# ProPrj_GTStoppuhr_v0_1.net
KiCad netlist of a schematic drawn in EasyEDA Pro
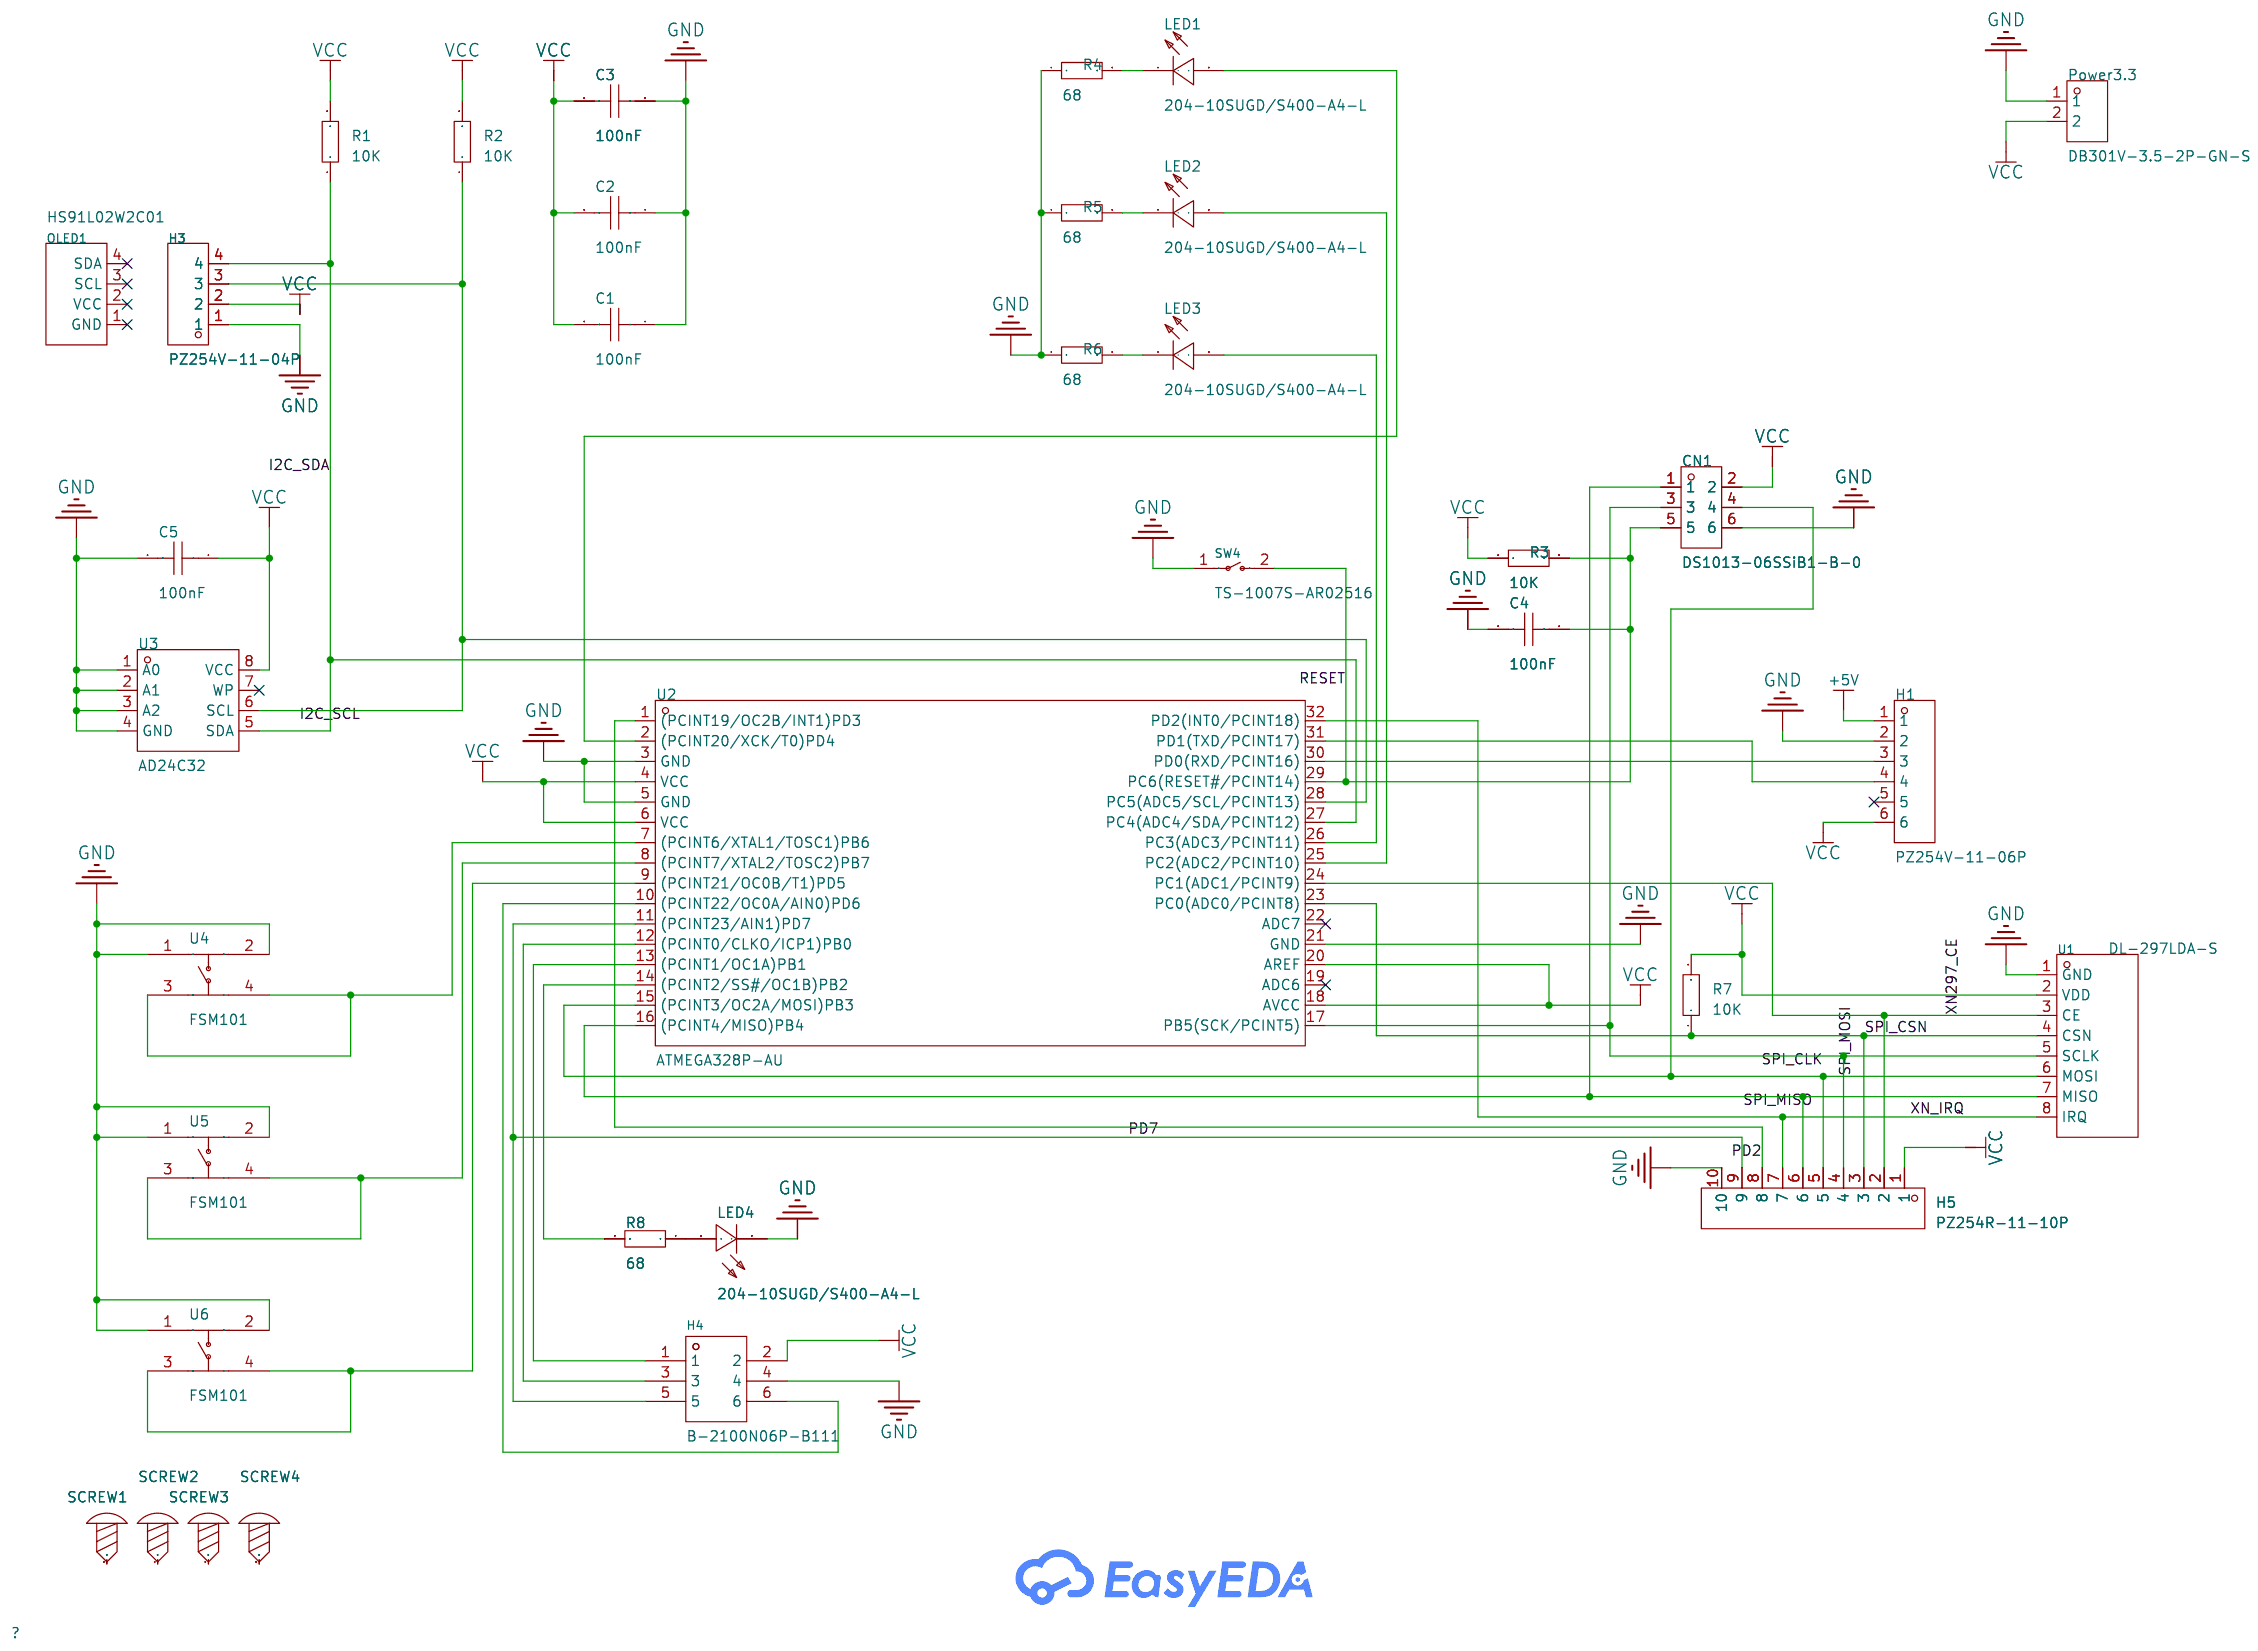
[diagram p0: schematic sheet]

(export (version "E")
  (design (tool "Eeschema 10.0.6"))
  (components
    (comp (ref "C1")
      (value "100nF")
      (footprint "easyedapro:C0603")
      (libsource (lib "easyedapro") (part "CAP"))
    )
    (comp (ref "C2")
      (value "100nF")
      (footprint "easyedapro:C0603")
      (libsource (lib "easyedapro") (part "CAP"))
    )
    (comp (ref "C3")
      (value "100nF")
      (footprint "easyedapro:C0603")
      (libsource (lib "easyedapro") (part "CAP"))
    )
    (comp (ref "C4")
      (value "100nF")
      (footprint "easyedapro:C0603")
      (libsource (lib "easyedapro") (part "CAP"))
    )
    (comp (ref "C5")
      (value "100nF")
      (footprint "easyedapro:C0603")
      (libsource (lib "easyedapro") (part "CAP"))
    )
    (comp (ref "CN1")
      (value "DS1013-06SSiB1-B-0")
      (footprint "easyedapro:IDC-TH_6P-P2.54_DS1013-06SSIB1-B-0")
      (fields (field (name "Manufacturer") "CONNFLY"))
      (libsource (lib "easyedapro") (part "DS1013-06SSIB1-B-0"))
    )
    (comp (ref "H1")
      (value "PZ254V-11-06P")
      (footprint "easyedapro:HDR-TH_6P-P2.54-V-M")
      (fields (field (name "Manufacturer") "XFCN(兴飞)"))
      (libsource (lib "easyedapro") (part "PZ254V-11-06P"))
    )
    (comp (ref "H3")
      (value "PZ254V-11-04P")
      (footprint "easyedapro:HDR-TH_4P-P2.54-V-M")
      (fields (field (name "Manufacturer") "XFCN(兴飞)"))
      (libsource (lib "easyedapro") (part "PZ254V-11-04P_C2691448"))
    )
    (comp (ref "H4")
      (value "B-2100N06P-B111")
      (footprint "easyedapro:HDR-SMD_6P-P2.54-V-M-R2-C3-S2.54-LS7.3")
      (fields (field (name "Manufacturer") "Ckmtw(灿科盟)"))
      (libsource (lib "easyedapro") (part "210SMT-2*3P Gold-plated black"))
    )
    (comp (ref "H5")
      (value "PZ254R-11-10P")
      (footprint "easyedapro:HDR-TH_10P-P2.54-H-M-W10.4")
      (fields (field (name "Manufacturer") "XFCN(兴飞)"))
      (libsource (lib "easyedapro") (part "PZ254R-11-10P"))
    )
    (comp (ref "LED1")
      (value "204-10SUGD/S400-A4-L")
      (footprint "easyedapro:LED-TH_BD3.9-P2.54-RD")
      (fields (field (name "Manufacturer") "EVERLIGHT(亿光)"))
      (libsource (lib "easyedapro") (part "204-10SUGD/S400-A4-L"))
    )
    (comp (ref "LED2")
      (value "204-10SUGD/S400-A4-L")
      (footprint "easyedapro:LED-TH_BD3.9-P2.54-RD")
      (fields (field (name "Manufacturer") "EVERLIGHT(亿光)"))
      (libsource (lib "easyedapro") (part "204-10SUGD/S400-A4-L"))
    )
    (comp (ref "LED3")
      (value "204-10SUGD/S400-A4-L")
      (footprint "easyedapro:LED-TH_BD3.9-P2.54-RD")
      (fields (field (name "Manufacturer") "EVERLIGHT(亿光)"))
      (libsource (lib "easyedapro") (part "204-10SUGD/S400-A4-L"))
    )
    (comp (ref "LED4")
      (value "204-10SUGD/S400-A4-L")
      (footprint "easyedapro:LED-TH_BD3.9-P2.54-RD")
      (fields (field (name "Manufacturer") "EVERLIGHT(亿光)"))
      (libsource (lib "easyedapro") (part "204-10SUGD/S400-A4-L"))
    )
    (comp (ref "OLED1")
      (value "HS91L02W2C01")
      (footprint "easyedapro:OLED-TH_L38.0-W12.0_HS91L02W2C01")
      (fields (field (name "Manufacturer") "HS(汉昇)"))
      (libsource (lib "easyedapro") (part "HS91L02W2C01"))
    )
    (comp (ref "Power3.3")
      (value "DB301V-3.5-2P-GN-S")
      (footprint "easyedapro:CONN-TH_2P-P3.50_DIBO_DB127S-3.5-2P-GN")
      (fields (field (name "Manufacturer") "DORABO(地博电气)"))
      (libsource (lib "easyedapro") (part "DB127S-3.5-2P-GN"))
    )
    (comp (ref "R1") (value "10K") (footprint "easyedapro:R0603") (libsource (lib "easyedapro") (part "Res")))
    (comp (ref "R2") (value "10K") (footprint "easyedapro:R0603") (libsource (lib "easyedapro") (part "Res")))
    (comp (ref "R3") (value "10K") (footprint "easyedapro:R0603") (libsource (lib "easyedapro") (part "Res")))
    (comp (ref "R4") (value "68") (footprint "easyedapro:R0603") (libsource (lib "easyedapro") (part "Res")))
    (comp (ref "R5") (value "68") (footprint "easyedapro:R0603") (libsource (lib "easyedapro") (part "Res")))
    (comp (ref "R6") (value "68") (footprint "easyedapro:R0603") (libsource (lib "easyedapro") (part "Res")))
    (comp (ref "R7") (value "10K") (footprint "easyedapro:R0603") (libsource (lib "easyedapro") (part "Res")))
    (comp (ref "R8") (value "68") (footprint "easyedapro:R0603") (libsource (lib "easyedapro") (part "Res")))
    (comp (ref "SCREW1")
      (value "~")
      (footprint "easyedapro:Screw-Hole-M4")
      (description "Screw-Hole-M4")
      (libsource (lib "easyedapro") (part "Screw-Hole"))
    )
    (comp (ref "SCREW2")
      (value "~")
      (footprint "easyedapro:Screw-Hole-M4")
      (description "Screw-Hole-M4")
      (libsource (lib "easyedapro") (part "Screw-Hole"))
    )
    (comp (ref "SCREW3")
      (value "~")
      (footprint "easyedapro:Screw-Hole-M4")
      (description "Screw-Hole-M4")
      (libsource (lib "easyedapro") (part "Screw-Hole"))
    )
    (comp (ref "SCREW4")
      (value "~")
      (footprint "easyedapro:Screw-Hole-M4")
      (description "Screw-Hole-M4")
      (libsource (lib "easyedapro") (part "Screw-Hole"))
    )
    (comp (ref "SW4")
      (value "TS-1007S-AR02516")
      (footprint "easyedapro:SW-SMD_L6.1-W3.6-LS7.9")
      (fields (field (name "Manufacturer") "XUNPU(讯普)"))
      (libsource (lib "easyedapro") (part "TS-1007S-AR02516"))
    )
    (comp (ref "U1")
      (value "DL-297LDA-S")
      (footprint "easyedapro:WIRELM-SMD_DL-297LDA-S")
      (fields (field (name "Manufacturer") "DreamLNK(骏晔科技)"))
      (libsource (lib "easyedapro") (part "DL-297LDA-S"))
    )
    (comp (ref "U2")
      (value "ATMEGA328P-AU")
      (footprint "easyedapro:TQFP-32_L7.0-W7.0-P0.80-LS9.0-BL")
      (fields (field (name "Manufacturer") "MICROCHIP(美国微芯)"))
      (libsource (lib "easyedapro") (part "ATMEGA328P-AU"))
    )
    (comp (ref "U3")
      (value "AD24C32")
      (footprint "easyedapro:SOIC-8_L4.9-W3.9-P1.27-LS6.2-BL")
      (fields (field (name "Manufacturer") "IDCHIP(英锐芯)"))
      (libsource (lib "easyedapro") (part "AD24C32"))
    )
    (comp (ref "U4")
      (value "FSM101")
      (footprint "easyedapro:SW-TH_4P-L12.0-W12.0-P5.00-LS12.5")
      (fields (field (name "Manufacturer") "TE Connectivity(泰科电子)"))
      (libsource (lib "easyedapro") (part "FSM101"))
    )
    (comp (ref "U5")
      (value "FSM101")
      (footprint "easyedapro:SW-TH_4P-L12.0-W12.0-P5.00-LS12.5")
      (fields (field (name "Manufacturer") "TE Connectivity(泰科电子)"))
      (libsource (lib "easyedapro") (part "FSM101"))
    )
    (comp (ref "U6")
      (value "FSM101")
      (footprint "easyedapro:SW-TH_4P-L12.0-W12.0-P5.00-LS12.5")
      (fields (field (name "Manufacturer") "TE Connectivity(泰科电子)"))
      (libsource (lib "easyedapro") (part "FSM101"))
    )
  )
  (nets
    (net (code "1") (name "+5V") (class "Default")
      (node (ref "H1") (pin "1") (pinfunction "1_1") (pintype "unspecified"))
    )
    (net (code "2") (name "/I2C_SCL") (class "Default")
      (node (ref "H3") (pin "3") (pinfunction "3_3") (pintype "input"))
      (node (ref "R2") (pin "1") (pinfunction "1_1") (pintype "input"))
      (node (ref "U2") (pin "28") (pinfunction "PC5(ADC5/SCL/PCINT13)_28") (pintype "unspecified"))
      (node (ref "U3") (pin "6") (pinfunction "SCL_6") (pintype "unspecified"))
    )
    (net (code "3") (name "/I2C_SDA") (class "Default")
      (node (ref "H3") (pin "4") (pinfunction "4_4") (pintype "input"))
      (node (ref "R1") (pin "1") (pinfunction "1_1") (pintype "input"))
      (node (ref "U2") (pin "27") (pinfunction "PC4(ADC4/SDA/PCINT12)_27") (pintype "unspecified"))
      (node (ref "U3") (pin "5") (pinfunction "SDA_5") (pintype "unspecified"))
    )
    (net (code "4") (name "/PD2") (class "Default")
      (node (ref "H5") (pin "8") (pinfunction "8_8") (pintype "unspecified"))
      (node (ref "U2") (pin "1") (pinfunction "(PCINT19/OC2B/INT1)PD3_1") (pintype "unspecified"))
    )
    (net (code "5") (name "/PD7") (class "Default")
      (node (ref "H4") (pin "5") (pinfunction "5_5") (pintype "input"))
      (node (ref "H5") (pin "9") (pinfunction "9_9") (pintype "unspecified"))
      (node (ref "U2") (pin "11") (pinfunction "(PCINT23/AIN1)PD7_11") (pintype "unspecified"))
    )
    (net (code "6") (name "/RESET") (class "Default")
      (node (ref "C4") (pin "1") (pinfunction "1_1") (pintype "input"))
      (node (ref "CN1") (pin "5") (pinfunction "5_5") (pintype "unspecified"))
      (node (ref "R3") (pin "2") (pinfunction "2_2") (pintype "input"))
      (node (ref "SW4") (pin "2") (pinfunction "2_2") (pintype "input"))
      (node (ref "U2") (pin "29") (pinfunction "PC6(RESET#/PCINT14)_29") (pintype "unspecified"))
    )
    (net (code "7") (name "/SPI_CLK") (class "Default")
      (node (ref "CN1") (pin "3") (pinfunction "3_3") (pintype "unspecified"))
      (node (ref "H5") (pin "4") (pinfunction "4_4") (pintype "unspecified"))
      (node (ref "U1") (pin "5") (pinfunction "SCLK_5") (pintype "input"))
      (node (ref "U2") (pin "17") (pinfunction "PB5(SCK/PCINT5)_17") (pintype "unspecified"))
    )
    (net (code "8") (name "/SPI_CSN") (class "Default")
      (node (ref "H5") (pin "3") (pinfunction "3_3") (pintype "unspecified"))
      (node (ref "R7") (pin "1") (pinfunction "1_1") (pintype "input"))
      (node (ref "U1") (pin "4") (pinfunction "CSN_4") (pintype "input"))
      (node (ref "U2") (pin "23") (pinfunction "PC0(ADC0/PCINT8)_23") (pintype "unspecified"))
    )
    (net (code "9") (name "/SPI_MISO") (class "Default")
      (node (ref "CN1") (pin "1") (pinfunction "1_1") (pintype "unspecified"))
      (node (ref "H5") (pin "6") (pinfunction "6_6") (pintype "unspecified"))
      (node (ref "U1") (pin "7") (pinfunction "MISO_7") (pintype "input"))
      (node (ref "U2") (pin "16") (pinfunction "(PCINT4/MISO)PB4_16") (pintype "unspecified"))
    )
    (net (code "10") (name "/SPI_MOSI") (class "Default")
      (node (ref "CN1") (pin "4") (pinfunction "4_4") (pintype "unspecified"))
      (node (ref "H5") (pin "5") (pinfunction "5_5") (pintype "unspecified"))
      (node (ref "U1") (pin "6") (pinfunction "MOSI_6") (pintype "input"))
      (node (ref "U2") (pin "15") (pinfunction "(PCINT3/OC2A/MOSI)PB3_15") (pintype "unspecified"))
    )
    (net (code "11") (name "/XN297_CE") (class "Default")
      (node (ref "H5") (pin "2") (pinfunction "2_2") (pintype "unspecified"))
      (node (ref "U1") (pin "3") (pinfunction "CE_3") (pintype "input"))
      (node (ref "U2") (pin "24") (pinfunction "PC1(ADC1/PCINT9)_24") (pintype "unspecified"))
    )
    (net (code "12") (name "/XN_IRQ") (class "Default")
      (node (ref "H5") (pin "7") (pinfunction "7_7") (pintype "unspecified"))
      (node (ref "U1") (pin "8") (pinfunction "IRQ_8") (pintype "input"))
      (node (ref "U2") (pin "32") (pinfunction "PD2(INT0/PCINT18)_32") (pintype "unspecified"))
    )
    (net (code "13") (name "GND") (class "Default")
      (node (ref "C1") (pin "1") (pinfunction "1_1") (pintype "input"))
      (node (ref "C2") (pin "1") (pinfunction "1_1") (pintype "input"))
      (node (ref "C3") (pin "2") (pinfunction "2_2") (pintype "input"))
      (node (ref "C4") (pin "2") (pinfunction "2_2") (pintype "input"))
      (node (ref "C5") (pin "2") (pinfunction "2_2") (pintype "input"))
      (node (ref "CN1") (pin "6") (pinfunction "6_6") (pintype "unspecified"))
      (node (ref "H1") (pin "2") (pinfunction "2_2") (pintype "unspecified"))
      (node (ref "H3") (pin "1") (pinfunction "1_1") (pintype "input"))
      (node (ref "H4") (pin "4") (pinfunction "4_4") (pintype "input"))
      (node (ref "H5") (pin "10") (pinfunction "10_10") (pintype "unspecified"))
      (node (ref "LED4") (pin "1") (pinfunction "-_1") (pintype "input"))
      (node (ref "Power3.3") (pin "1") (pinfunction "1_1") (pintype "unspecified"))
      (node (ref "R4") (pin "1") (pinfunction "1_1") (pintype "input"))
      (node (ref "R5") (pin "1") (pinfunction "1_1") (pintype "input"))
      (node (ref "R6") (pin "1") (pinfunction "1_1") (pintype "input"))
      (node (ref "SW4") (pin "1") (pinfunction "1_1") (pintype "input"))
      (node (ref "U1") (pin "1") (pinfunction "GND_1") (pintype "input"))
      (node (ref "U2") (pin "21") (pinfunction "GND_21") (pintype "unspecified"))
      (node (ref "U2") (pin "3") (pinfunction "GND_3") (pintype "unspecified"))
      (node (ref "U2") (pin "5") (pinfunction "GND_5") (pintype "unspecified"))
      (node (ref "U3") (pin "1") (pinfunction "A0_1") (pintype "unspecified"))
      (node (ref "U3") (pin "2") (pinfunction "A1_2") (pintype "unspecified"))
      (node (ref "U3") (pin "3") (pinfunction "A2_3") (pintype "unspecified"))
      (node (ref "U3") (pin "4") (pinfunction "GND_4") (pintype "unspecified"))
      (node (ref "U4") (pin "1") (pinfunction "1_1") (pintype "unspecified"))
      (node (ref "U4") (pin "2") (pinfunction "2_2") (pintype "unspecified"))
      (node (ref "U5") (pin "1") (pinfunction "1_1") (pintype "unspecified"))
      (node (ref "U5") (pin "2") (pinfunction "2_2") (pintype "unspecified"))
      (node (ref "U6") (pin "1") (pinfunction "1_1") (pintype "unspecified"))
      (node (ref "U6") (pin "2") (pinfunction "2_2") (pintype "unspecified"))
    )
    (net (code "14") (name "Net-(LED1-+)") (class "Default")
      (node (ref "LED1") (pin "2") (pinfunction "+_2") (pintype "input"))
      (node (ref "U2") (pin "2") (pinfunction "(PCINT20/XCK/T0)PD4_2") (pintype "unspecified"))
    )
    (net (code "15") (name "Net-(LED1--)") (class "Default")
      (node (ref "LED1") (pin "1") (pinfunction "-_1") (pintype "input"))
      (node (ref "R4") (pin "2") (pinfunction "2_2") (pintype "input"))
    )
    (net (code "16") (name "Net-(LED2-+)") (class "Default")
      (node (ref "LED2") (pin "2") (pinfunction "+_2") (pintype "input"))
      (node (ref "U2") (pin "25") (pinfunction "PC2(ADC2/PCINT10)_25") (pintype "unspecified"))
    )
    (net (code "17") (name "Net-(LED2--)") (class "Default")
      (node (ref "LED2") (pin "1") (pinfunction "-_1") (pintype "input"))
      (node (ref "R5") (pin "2") (pinfunction "2_2") (pintype "input"))
    )
    (net (code "18") (name "Net-(LED3-+)") (class "Default")
      (node (ref "LED3") (pin "2") (pinfunction "+_2") (pintype "input"))
      (node (ref "U2") (pin "26") (pinfunction "PC3(ADC3/PCINT11)_26") (pintype "unspecified"))
    )
    (net (code "19") (name "Net-(LED3--)") (class "Default")
      (node (ref "LED3") (pin "1") (pinfunction "-_1") (pintype "input"))
      (node (ref "R6") (pin "2") (pinfunction "2_2") (pintype "input"))
    )
    (net (code "20") (name "Net-(LED4-+)") (class "Default")
      (node (ref "LED4") (pin "2") (pinfunction "+_2") (pintype "input"))
      (node (ref "R8") (pin "1") (pinfunction "1_1") (pintype "input"))
    )
    (net (code "21") (name "Net-(U2-(PCINT0{slash}CLKO{slash}ICP1)PB0)") (class "Default")
      (node (ref "H4") (pin "3") (pinfunction "3_3") (pintype "input"))
      (node (ref "U2") (pin "12") (pinfunction "(PCINT0/CLKO/ICP1)PB0_12") (pintype "unspecified"))
    )
    (net (code "22") (name "Net-(U2-(PCINT1{slash}OC1A)PB1)") (class "Default")
      (node (ref "H4") (pin "1") (pinfunction "1_1") (pintype "input"))
      (node (ref "U2") (pin "13") (pinfunction "(PCINT1/OC1A)PB1_13") (pintype "unspecified"))
    )
    (net (code "23") (name "Net-(U2-(PCINT2{slash}SS#{slash}OC1B)PB2)") (class "Default")
      (node (ref "R8") (pin "2") (pinfunction "2_2") (pintype "input"))
      (node (ref "U2") (pin "14") (pinfunction "(PCINT2/SS#/OC1B)PB2_14") (pintype "unspecified"))
    )
    (net (code "24") (name "Net-(U2-(PCINT6{slash}XTAL1{slash}TOSC1)PB6)") (class "Default")
      (node (ref "U2") (pin "7") (pinfunction "(PCINT6/XTAL1/TOSC1)PB6_7") (pintype "unspecified"))
      (node (ref "U4") (pin "3") (pinfunction "3_3") (pintype "unspecified"))
      (node (ref "U4") (pin "4") (pinfunction "4_4") (pintype "unspecified"))
    )
    (net (code "25") (name "Net-(U2-(PCINT7{slash}XTAL2{slash}TOSC2)PB7)") (class "Default")
      (node (ref "U2") (pin "8") (pinfunction "(PCINT7/XTAL2/TOSC2)PB7_8") (pintype "unspecified"))
      (node (ref "U5") (pin "3") (pinfunction "3_3") (pintype "unspecified"))
      (node (ref "U5") (pin "4") (pinfunction "4_4") (pintype "unspecified"))
    )
    (net (code "26") (name "Net-(U2-(PCINT21{slash}OC0B{slash}T1)PD5)") (class "Default")
      (node (ref "U2") (pin "9") (pinfunction "(PCINT21/OC0B/T1)PD5_9") (pintype "unspecified"))
      (node (ref "U6") (pin "3") (pinfunction "3_3") (pintype "unspecified"))
      (node (ref "U6") (pin "4") (pinfunction "4_4") (pintype "unspecified"))
    )
    (net (code "27") (name "Net-(U2-(PCINT22{slash}OC0A{slash}AIN0)PD6)") (class "Default")
      (node (ref "H4") (pin "6") (pinfunction "6_6") (pintype "input"))
      (node (ref "U2") (pin "10") (pinfunction "(PCINT22/OC0A/AIN0)PD6_10") (pintype "unspecified"))
    )
    (net (code "28") (name "Net-(U2-PD0(RXD{slash}PCINT16))") (class "Default")
      (node (ref "H1") (pin "3") (pinfunction "3_3") (pintype "unspecified"))
      (node (ref "U2") (pin "30") (pinfunction "PD0(RXD/PCINT16)_30") (pintype "unspecified"))
    )
    (net (code "29") (name "Net-(U2-PD1(TXD{slash}PCINT17))") (class "Default")
      (node (ref "H1") (pin "4") (pinfunction "4_4") (pintype "unspecified"))
      (node (ref "U2") (pin "31") (pinfunction "PD1(TXD/PCINT17)_31") (pintype "unspecified"))
    )
    (net (code "30") (name "VCC") (class "Default")
      (node (ref "C1") (pin "2") (pinfunction "2_2") (pintype "input"))
      (node (ref "C2") (pin "2") (pinfunction "2_2") (pintype "input"))
      (node (ref "C3") (pin "1") (pinfunction "1_1") (pintype "input"))
      (node (ref "C5") (pin "1") (pinfunction "1_1") (pintype "input"))
      (node (ref "CN1") (pin "2") (pinfunction "2_2") (pintype "unspecified"))
      (node (ref "H1") (pin "6") (pinfunction "6_6") (pintype "unspecified"))
      (node (ref "H3") (pin "2") (pinfunction "2_2") (pintype "input"))
      (node (ref "H4") (pin "2") (pinfunction "2_2") (pintype "input"))
      (node (ref "H5") (pin "1") (pinfunction "1_1") (pintype "unspecified"))
      (node (ref "Power3.3") (pin "2") (pinfunction "2_2") (pintype "unspecified"))
      (node (ref "R1") (pin "2") (pinfunction "2_2") (pintype "input"))
      (node (ref "R2") (pin "2") (pinfunction "2_2") (pintype "input"))
      (node (ref "R3") (pin "1") (pinfunction "1_1") (pintype "input"))
      (node (ref "R7") (pin "2") (pinfunction "2_2") (pintype "input"))
      (node (ref "U1") (pin "2") (pinfunction "VDD_2") (pintype "input"))
      (node (ref "U2") (pin "18") (pinfunction "AVCC_18") (pintype "unspecified"))
      (node (ref "U2") (pin "20") (pinfunction "AREF_20") (pintype "unspecified"))
      (node (ref "U2") (pin "4") (pinfunction "VCC_4") (pintype "unspecified"))
      (node (ref "U2") (pin "6") (pinfunction "VCC_6") (pintype "unspecified"))
      (node (ref "U3") (pin "8") (pinfunction "VCC_8") (pintype "unspecified"))
    )
    (net (code "31") (name "unconnected-(H1-Pad5)") (class "Default")
      (node (ref "H1") (pin "5") (pinfunction "5_5") (pintype "unspecified+no_connect"))
    )
    (net (code "32") (name "unconnected-(OLED1-GND-Pad1)") (class "Default")
      (node (ref "OLED1") (pin "1") (pinfunction "GND_1") (pintype "input+no_connect"))
    )
    (net (code "33") (name "unconnected-(OLED1-SCL-Pad3)") (class "Default")
      (node (ref "OLED1") (pin "3") (pinfunction "SCL_3") (pintype "input+no_connect"))
    )
    (net (code "34") (name "unconnected-(OLED1-SDA-Pad4)") (class "Default")
      (node (ref "OLED1") (pin "4") (pinfunction "SDA_4") (pintype "input+no_connect"))
    )
    (net (code "35") (name "unconnected-(OLED1-VCC-Pad2)") (class "Default")
      (node (ref "OLED1") (pin "2") (pinfunction "VCC_2") (pintype "input+no_connect"))
    )
    (net (code "36") (name "unconnected-(SCREW1-Pad1)") (class "Default")
      (node (ref "SCREW1") (pin "1") (pinfunction "1_1") (pintype "input"))
    )
    (net (code "37") (name "unconnected-(SCREW2-Pad1)") (class "Default")
      (node (ref "SCREW2") (pin "1") (pinfunction "1_1") (pintype "input"))
    )
    (net (code "38") (name "unconnected-(SCREW3-Pad1)") (class "Default")
      (node (ref "SCREW3") (pin "1") (pinfunction "1_1") (pintype "input"))
    )
    (net (code "39") (name "unconnected-(SCREW4-Pad1)") (class "Default")
      (node (ref "SCREW4") (pin "1") (pinfunction "1_1") (pintype "input"))
    )
    (net (code "40") (name "unconnected-(U2-ADC6-Pad19)") (class "Default")
      (node (ref "U2") (pin "19") (pinfunction "ADC6_19") (pintype "unspecified+no_connect"))
    )
    (net (code "41") (name "unconnected-(U2-ADC7-Pad22)") (class "Default")
      (node (ref "U2") (pin "22") (pinfunction "ADC7_22") (pintype "unspecified+no_connect"))
    )
    (net (code "42") (name "unconnected-(U3-WP-Pad7)") (class "Default")
      (node (ref "U3") (pin "7") (pinfunction "WP_7") (pintype "unspecified+no_connect"))
    )
  )
)
